# board1.net
KiCad netlist of a schematic drawn in EAGLE
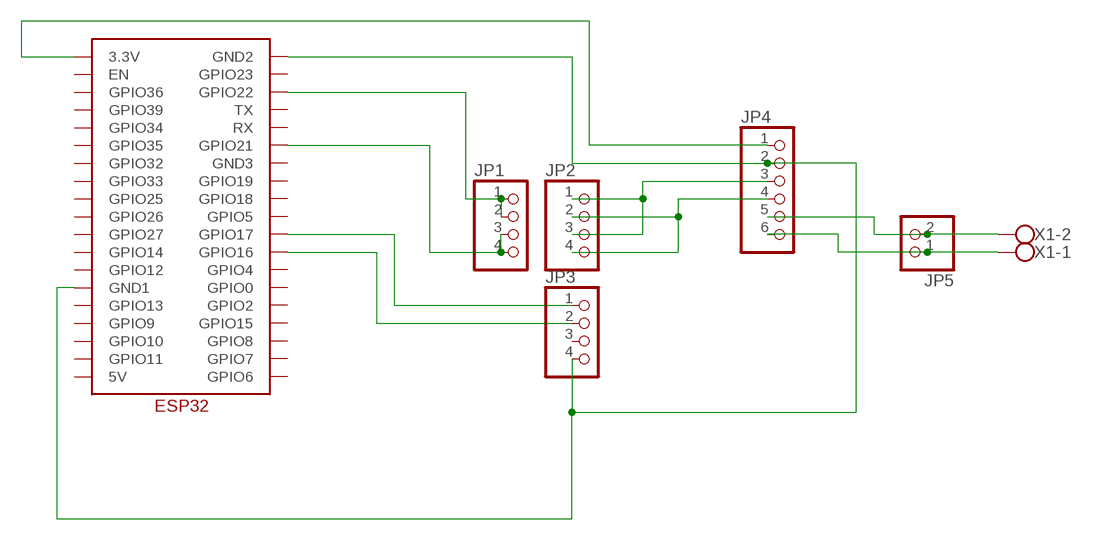
[diagram p0: schematic, sheet 1]

(export (version "E")
  (design (tool "Eeschema 10.0.6"))
  (components
    (comp (ref "JP1")
      (value "PINHD-1X4")
      (footprint "eagle-import:1X04")
      (libsource (lib "eagle-import") (part "PINHD-1X4"))
    )
    (comp (ref "JP2")
      (value "PINHD-1X4")
      (footprint "eagle-import:1X04")
      (libsource (lib "eagle-import") (part "PINHD-1X4"))
    )
    (comp (ref "JP3")
      (value "PINHD-1X4")
      (footprint "eagle-import:1X04")
      (libsource (lib "eagle-import") (part "PINHD-1X4"))
    )
    (comp (ref "JP4")
      (value "PINHD-1X6")
      (footprint "eagle-import:1X06")
      (libsource (lib "eagle-import") (part "PINHD-1X6"))
    )
    (comp (ref "JP5")
      (value "PINHD-1X2")
      (footprint "eagle-import:1X02")
      (libsource (lib "eagle-import") (part "PINHD-1X2"))
    )
    (comp (ref "U$1")
      (value "ESP32_GRBL")
      (footprint "eagle-import:ESP32_GRBL")
      (libsource (lib "eagle-import") (part "ESP32_GRBL"))
    )
    (comp (ref "X1")
      (value "W237-102")
      (footprint "eagle-import:W237-102")
      (fields (field (name "MPN") "237-102"))
      (libsource (lib "eagle-import") (part "W237-102"))
    )
  )
  (nets
    (net (code "1") (name "Net-(JP1-Pad1)") (class "Default")
      (node (ref "JP1") (pin "1") (pinfunction "1_1") (pintype "passive"))
      (node (ref "JP1") (pin "2") (pinfunction "2_2") (pintype "passive"))
      (node (ref "U$1") (pin "GPIO22") (pinfunction "GPIO22_GPIO22") (pintype "bidirectional"))
    )
    (net (code "2") (name "Net-(JP1-Pad3)") (class "Default")
      (node (ref "JP1") (pin "3") (pinfunction "3_3") (pintype "passive"))
      (node (ref "JP1") (pin "4") (pinfunction "4_4") (pintype "passive"))
      (node (ref "U$1") (pin "GPIO21") (pinfunction "GPIO21_GPIO21") (pintype "bidirectional"))
    )
    (net (code "3") (name "Net-(JP2-Pad1)") (class "Default")
      (node (ref "JP2") (pin "1") (pinfunction "1_1") (pintype "passive"))
      (node (ref "JP2") (pin "3") (pinfunction "3_3") (pintype "passive"))
      (node (ref "JP4") (pin "3") (pinfunction "3_3") (pintype "passive"))
    )
    (net (code "4") (name "Net-(JP2-Pad2)") (class "Default")
      (node (ref "JP2") (pin "2") (pinfunction "2_2") (pintype "passive"))
      (node (ref "JP2") (pin "4") (pinfunction "4_4") (pintype "passive"))
      (node (ref "JP4") (pin "4") (pinfunction "4_4") (pintype "passive"))
    )
    (net (code "5") (name "Net-(JP3-Pad1)") (class "Default")
      (node (ref "JP3") (pin "1") (pinfunction "1_1") (pintype "passive"))
      (node (ref "U$1") (pin "GPIO17") (pinfunction "GPIO17_GPIO17") (pintype "bidirectional"))
    )
    (net (code "6") (name "Net-(JP3-Pad2)") (class "Default")
      (node (ref "JP3") (pin "2") (pinfunction "2_2") (pintype "passive"))
      (node (ref "U$1") (pin "GPIO16") (pinfunction "GPIO16_GPIO16") (pintype "bidirectional"))
    )
    (net (code "7") (name "Net-(JP3-Pad4)") (class "Default")
      (node (ref "JP3") (pin "4") (pinfunction "4_4") (pintype "passive"))
      (node (ref "JP4") (pin "2") (pinfunction "2_2") (pintype "passive"))
      (node (ref "U$1") (pin "GND1") (pinfunction "GND1_GND1") (pintype "bidirectional"))
      (node (ref "U$1") (pin "GND2") (pinfunction "GND2_GND2") (pintype "bidirectional"))
    )
    (net (code "8") (name "Net-(JP4-Pad1)") (class "Default")
      (node (ref "JP4") (pin "1") (pinfunction "1_1") (pintype "passive"))
      (node (ref "U$1") (pin "3.3V") (pinfunction "3.3V_3.3V") (pintype "bidirectional"))
    )
    (net (code "9") (name "Net-(X1A-KL)") (class "Default")
      (node (ref "JP4") (pin "6") (pinfunction "6_6") (pintype "passive"))
      (node (ref "JP5") (pin "1") (pinfunction "1_1") (pintype "passive"))
      (node (ref "X1") (pin "1") (pinfunction "KL_1") (pintype "passive"))
    )
    (net (code "10") (name "Net-(X1B-KL)") (class "Default")
      (node (ref "JP4") (pin "5") (pinfunction "5_5") (pintype "passive"))
      (node (ref "JP5") (pin "2") (pinfunction "2_2") (pintype "passive"))
      (node (ref "X1") (pin "2") (pinfunction "KL_2") (pintype "passive"))
    )
    (net (code "11") (name "unconnected-(JP3-Pad3)") (class "Default")
      (node (ref "JP3") (pin "3") (pinfunction "3_3") (pintype "passive"))
    )
    (net (code "12") (name "unconnected-(U$1-Pad5V)") (class "Default")
      (node (ref "U$1") (pin "5V") (pinfunction "5V_5V") (pintype "bidirectional"))
    )
    (net (code "13") (name "unconnected-(U$1-PadEN)") (class "Default")
      (node (ref "U$1") (pin "EN") (pinfunction "EN_EN") (pintype "bidirectional"))
    )
    (net (code "14") (name "unconnected-(U$1-PadGND3)") (class "Default")
      (node (ref "U$1") (pin "GND3") (pinfunction "GND3_GND3") (pintype "bidirectional"))
    )
    (net (code "15") (name "unconnected-(U$1-PadGPIO0)") (class "Default")
      (node (ref "U$1") (pin "GPIO0") (pinfunction "GPIO0_GPIO0") (pintype "bidirectional"))
    )
    (net (code "16") (name "unconnected-(U$1-PadGPIO2)") (class "Default")
      (node (ref "U$1") (pin "GPIO2") (pinfunction "GPIO2_GPIO2") (pintype "bidirectional"))
    )
    (net (code "17") (name "unconnected-(U$1-PadGPIO4)") (class "Default")
      (node (ref "U$1") (pin "GPIO4") (pinfunction "GPIO4_GPIO4") (pintype "bidirectional"))
    )
    (net (code "18") (name "unconnected-(U$1-PadGPIO5)") (class "Default")
      (node (ref "U$1") (pin "GPIO5") (pinfunction "GPIO5_GPIO5") (pintype "bidirectional"))
    )
    (net (code "19") (name "unconnected-(U$1-PadGPIO6)") (class "Default")
      (node (ref "U$1") (pin "GPIO6") (pinfunction "GPIO6_GPIO6") (pintype "bidirectional"))
    )
    (net (code "20") (name "unconnected-(U$1-PadGPIO7)") (class "Default")
      (node (ref "U$1") (pin "GPIO7") (pinfunction "GPIO7_GPIO7") (pintype "bidirectional"))
    )
    (net (code "21") (name "unconnected-(U$1-PadGPIO8)") (class "Default")
      (node (ref "U$1") (pin "GPIO8") (pinfunction "GPIO8_GPIO8") (pintype "bidirectional"))
    )
    (net (code "22") (name "unconnected-(U$1-PadGPIO9)") (class "Default")
      (node (ref "U$1") (pin "GPIO9") (pinfunction "GPIO9_GPIO9") (pintype "bidirectional"))
    )
    (net (code "23") (name "unconnected-(U$1-PadGPIO10)") (class "Default")
      (node (ref "U$1") (pin "GPIO10") (pinfunction "GPIO10_GPIO10") (pintype "bidirectional"))
    )
    (net (code "24") (name "unconnected-(U$1-PadGPIO11)") (class "Default")
      (node (ref "U$1") (pin "GPIO11") (pinfunction "GPIO11_GPIO11") (pintype "bidirectional"))
    )
    (net (code "25") (name "unconnected-(U$1-PadGPIO12)") (class "Default")
      (node (ref "U$1") (pin "GPIO12") (pinfunction "GPIO12_GPIO12") (pintype "bidirectional"))
    )
    (net (code "26") (name "unconnected-(U$1-PadGPIO13)") (class "Default")
      (node (ref "U$1") (pin "GPIO13") (pinfunction "GPIO13_GPIO13") (pintype "bidirectional"))
    )
    (net (code "27") (name "unconnected-(U$1-PadGPIO14)") (class "Default")
      (node (ref "U$1") (pin "GPIO14") (pinfunction "GPIO14_GPIO14") (pintype "bidirectional"))
    )
    (net (code "28") (name "unconnected-(U$1-PadGPIO15)") (class "Default")
      (node (ref "U$1") (pin "GPIO15") (pinfunction "GPIO15_GPIO15") (pintype "bidirectional"))
    )
    (net (code "29") (name "unconnected-(U$1-PadGPIO18)") (class "Default")
      (node (ref "U$1") (pin "GPIO18") (pinfunction "GPIO18_GPIO18") (pintype "bidirectional"))
    )
    (net (code "30") (name "unconnected-(U$1-PadGPIO19)") (class "Default")
      (node (ref "U$1") (pin "GPIO19") (pinfunction "GPIO19_GPIO19") (pintype "bidirectional"))
    )
    (net (code "31") (name "unconnected-(U$1-PadGPIO23)") (class "Default")
      (node (ref "U$1") (pin "GPIO23") (pinfunction "GPIO23_GPIO23") (pintype "bidirectional"))
    )
    (net (code "32") (name "unconnected-(U$1-PadGPIO25)") (class "Default")
      (node (ref "U$1") (pin "GPIO25") (pinfunction "GPIO25_GPIO25") (pintype "bidirectional"))
    )
    (net (code "33") (name "unconnected-(U$1-PadGPIO26)") (class "Default")
      (node (ref "U$1") (pin "GPIO26") (pinfunction "GPIO26_GPIO26") (pintype "bidirectional"))
    )
    (net (code "34") (name "unconnected-(U$1-PadGPIO27)") (class "Default")
      (node (ref "U$1") (pin "GPIO27") (pinfunction "GPIO27_GPIO27") (pintype "bidirectional"))
    )
    (net (code "35") (name "unconnected-(U$1-PadGPIO32)") (class "Default")
      (node (ref "U$1") (pin "GPIO32") (pinfunction "GPIO32_GPIO32") (pintype "bidirectional"))
    )
    (net (code "36") (name "unconnected-(U$1-PadGPIO33)") (class "Default")
      (node (ref "U$1") (pin "GPIO33") (pinfunction "GPIO33_GPIO33") (pintype "bidirectional"))
    )
    (net (code "37") (name "unconnected-(U$1-PadGPIO34)") (class "Default")
      (node (ref "U$1") (pin "GPIO34") (pinfunction "GPIO34_GPIO34") (pintype "bidirectional"))
    )
    (net (code "38") (name "unconnected-(U$1-PadGPIO35)") (class "Default")
      (node (ref "U$1") (pin "GPIO35") (pinfunction "GPIO35_GPIO35") (pintype "bidirectional"))
    )
    (net (code "39") (name "unconnected-(U$1-PadGPIO36)") (class "Default")
      (node (ref "U$1") (pin "GPIO36") (pinfunction "GPIO36_GPIO36") (pintype "bidirectional"))
    )
    (net (code "40") (name "unconnected-(U$1-PadGPIO39)") (class "Default")
      (node (ref "U$1") (pin "GPIO39") (pinfunction "GPIO39_GPIO39") (pintype "bidirectional"))
    )
    (net (code "41") (name "unconnected-(U$1-PadRX)") (class "Default")
      (node (ref "U$1") (pin "RX") (pinfunction "RX_RX") (pintype "bidirectional"))
    )
    (net (code "42") (name "unconnected-(U$1-PadTX)") (class "Default")
      (node (ref "U$1") (pin "TX") (pinfunction "TX_TX") (pintype "bidirectional"))
    )
  )
)
